# Top_sheet.net
KiCad netlist of a schematic drawn in Altium Designer
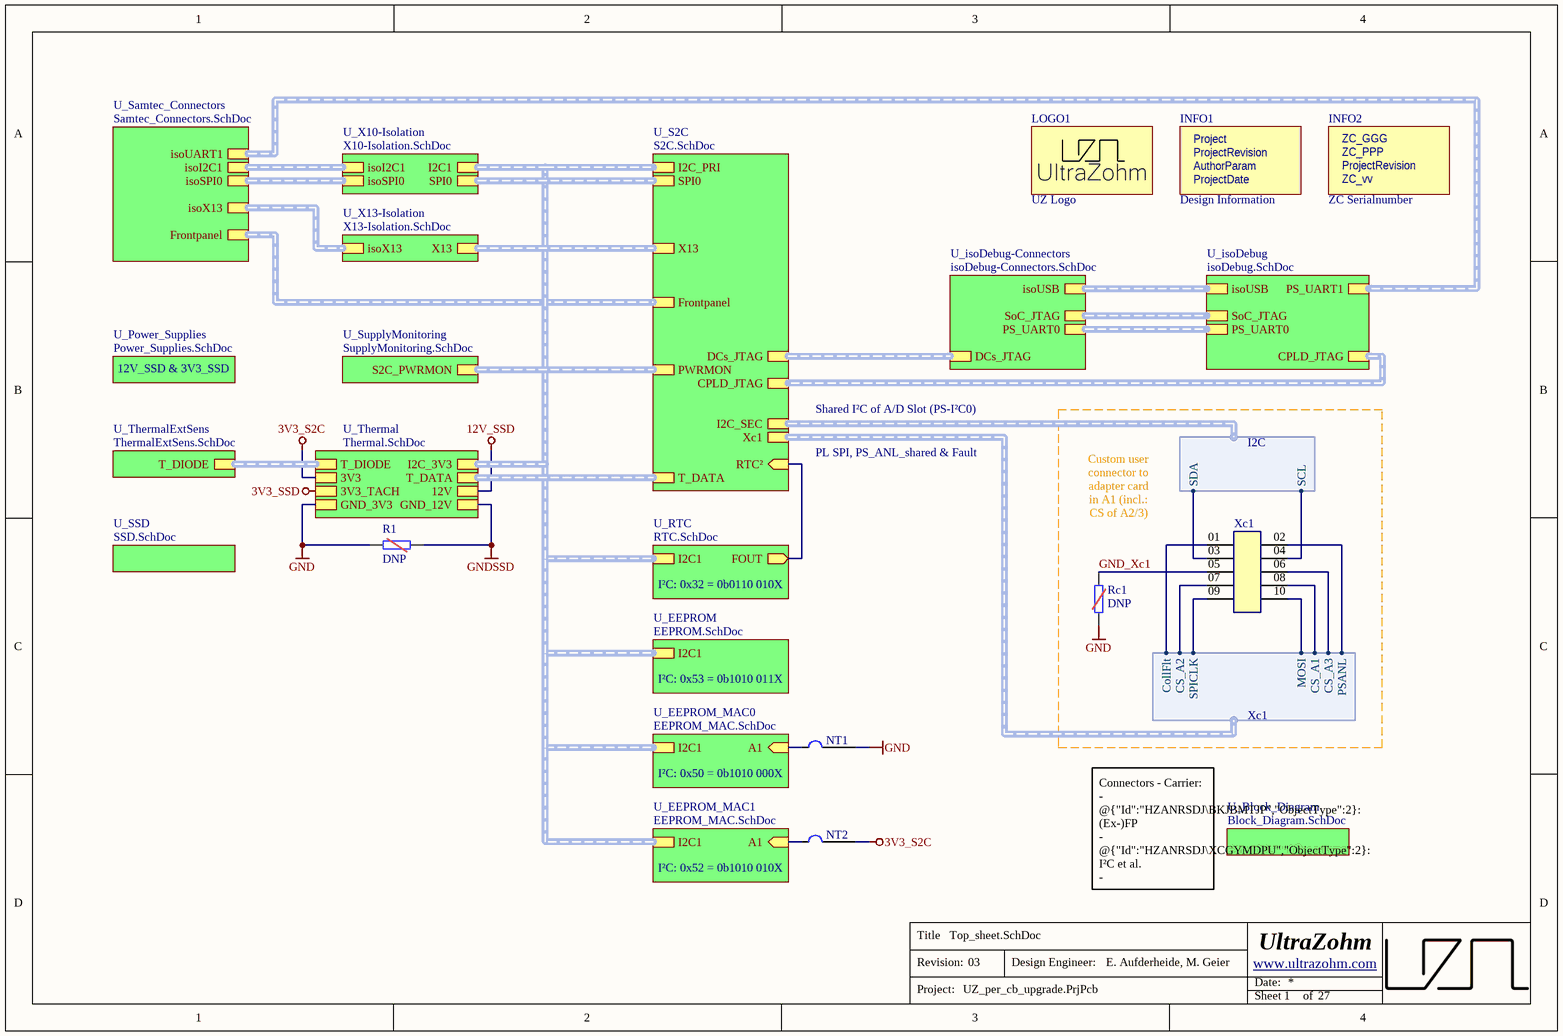
[diagram p0: Top_sheet.SchDoc]

(export (version "E")
  (design (tool "Eeschema 10.0.6"))
  (components
    (comp (ref "INFO1")
      (value "Design Information")
      (footprint "Design_info2")
      (fields (field (name "MANUFACTURER") "UltraZohm") (field (name "CREATED FROM") "MGremer"))
      (libsource (lib "user") (part "Design_info"))
    )
    (comp (ref "INFO2")
      (value "ZC Serialnumber")
      (footprint "ZC-Serial")
      (fields
        (field (name "MANUFACTURER PART NUMBER") "ZC-Serial")
        (field (name "MANUFACTURER") "UltraZohm")
        (field (name "CREATED FROM") "FRosner")
      )
      (libsource (lib "user") (part "ZC_Serial"))
    )
    (comp (ref "LOGO1")
      (value "UZ Logo")
      (footprint "UZ_Logo_small")
      (fields
        (field (name "MANUFACTURER PART NUMBER") "Logo small")
        (field (name "MANUFACTURER") "UltraZohm")
        (field (name "CREATED") "Jan2021_Liegmann")
        (field (name "CREATED FROM") "MGremer")
      )
      (libsource (lib "user") (part "UZ Logo"))
    )
    (comp (ref "NT1")
      (value "Net Tie 1 to 1")
      (footprint "1_to_1_NetTie_0.1mm")
      (description "Net Tie 1 to 1. Joins two nets without producing a DRC error or renaming one of the nets")
      (fields (field (name "CREATED BY") "MGeier"))
      (libsource (lib "user") (part "NetTie_1_to_1_small"))
    )
    (comp (ref "NT2")
      (value "Net Tie 1 to 1")
      (footprint "1_to_1_NetTie_0.1mm")
      (description "Net Tie 1 to 1. Joins two nets without producing a DRC error or renaming one of the nets")
      (fields (field (name "CREATED BY") "MGeier"))
      (libsource (lib "user") (part "NetTie_1_to_1_small"))
    )
    (comp (ref "R1")
      (value "DNP")
      (footprint "R_1206_TE-DNP")
      (description "Generic resistor (DNP)")
      (fields
        (field (name "MANUFACTURER PART NUMBER") "UZgen_R_1206_DNP")
        (field (name "MANUFACTURER") "UZgen")
        (field (name "CREATED FROM") "UZgenTool")
      )
      (libsource (lib "user") (part "RES-DNP"))
    )
    (comp (ref "Rc1")
      (value "DNP")
      (footprint "R_1206_TE-DNP")
      (description "Generic resistor (DNP)")
      (fields
        (field (name "MANUFACTURER PART NUMBER") "UZgen_R_1206_DNP")
        (field (name "MANUFACTURER") "UZgen")
        (field (name "CREATED FROM") "UZgenTool")
      )
      (libsource (lib "user") (part "RES-DNP"))
    )
    (comp (ref "Xc1")
      (value "PH 0.1\" SMD 2x05")
      (footprint "TSM-105-01-L-DV")
      (description "0.1\" Double-row Pin Header, 90°-to-PCB SMD, 2x05 Pins, 250V, 3A")
      (fields
        (field (name "MANUFACTURER PART NUMBER") "UZgen_Conn_PinHead_2x05_SMD_100mil_90deg")
        (field (name "MANUFACTURER") "UZgen")
        (field (name "CREATED FROM") "UZgenTool")
      )
      (libsource (lib "user") (part "PinHeader_2x05"))
    )
  )
  (nets
    (net (code "3") (name "/A1") (class "Default")
      (node (ref "NT1") (pin "1") (pinfunction "1_1") (pintype "passive"))
    )
    (net (code "4") (name "/A1_1") (class "Default")
      (node (ref "NT2") (pin "1") (pinfunction "1_1") (pintype "passive"))
    )
    (net (code "9") (name "/GND_Xc1") (class "Default")
      (node (ref "Rc1") (pin "1") (pinfunction "1_1") (pintype "passive"))
      (node (ref "Xc1") (pin "05") (pinfunction "05_05") (pintype "passive"))
    )
    (net (code "25") (name "3V3_S2C") (class "Default")
      (node (ref "NT2") (pin "2") (pinfunction "2_2") (pintype "passive"))
    )
    (net (code "28") (name "GND") (class "Default")
      (node (ref "NT1") (pin "2") (pinfunction "2_2") (pintype "passive"))
      (node (ref "R1") (pin "2") (pinfunction "2_2") (pintype "passive"))
      (node (ref "Rc1") (pin "2") (pinfunction "2_2") (pintype "passive"))
    )
    (net (code "29") (name "GNDSSD") (class "Default")
      (node (ref "R1") (pin "1") (pinfunction "1_1") (pintype "passive"))
    )
    (net (code "30") (name "unconnected-(Xc1-Pad01)") (class "Default")
      (node (ref "Xc1") (pin "01") (pinfunction "01_01") (pintype "passive"))
    )
    (net (code "31") (name "unconnected-(Xc1-Pad02)") (class "Default")
      (node (ref "Xc1") (pin "02") (pinfunction "02_02") (pintype "passive"))
    )
    (net (code "32") (name "unconnected-(Xc1-Pad03)") (class "Default")
      (node (ref "Xc1") (pin "03") (pinfunction "03_03") (pintype "passive"))
    )
    (net (code "33") (name "unconnected-(Xc1-Pad04)") (class "Default")
      (node (ref "Xc1") (pin "04") (pinfunction "04_04") (pintype "passive"))
    )
    (net (code "34") (name "unconnected-(Xc1-Pad06)") (class "Default")
      (node (ref "Xc1") (pin "06") (pinfunction "06_06") (pintype "passive"))
    )
    (net (code "35") (name "unconnected-(Xc1-Pad07)") (class "Default")
      (node (ref "Xc1") (pin "07") (pinfunction "07_07") (pintype "passive"))
    )
    (net (code "36") (name "unconnected-(Xc1-Pad08)") (class "Default")
      (node (ref "Xc1") (pin "08") (pinfunction "08_08") (pintype "passive"))
    )
    (net (code "37") (name "unconnected-(Xc1-Pad09)") (class "Default")
      (node (ref "Xc1") (pin "09") (pinfunction "09_09") (pintype "passive"))
    )
    (net (code "38") (name "unconnected-(Xc1-Pad10)") (class "Default")
      (node (ref "Xc1") (pin "10") (pinfunction "10_10") (pintype "passive"))
    )
  )
)
